# mds2.net
KiCad netlist of a schematic drawn in EAGLE
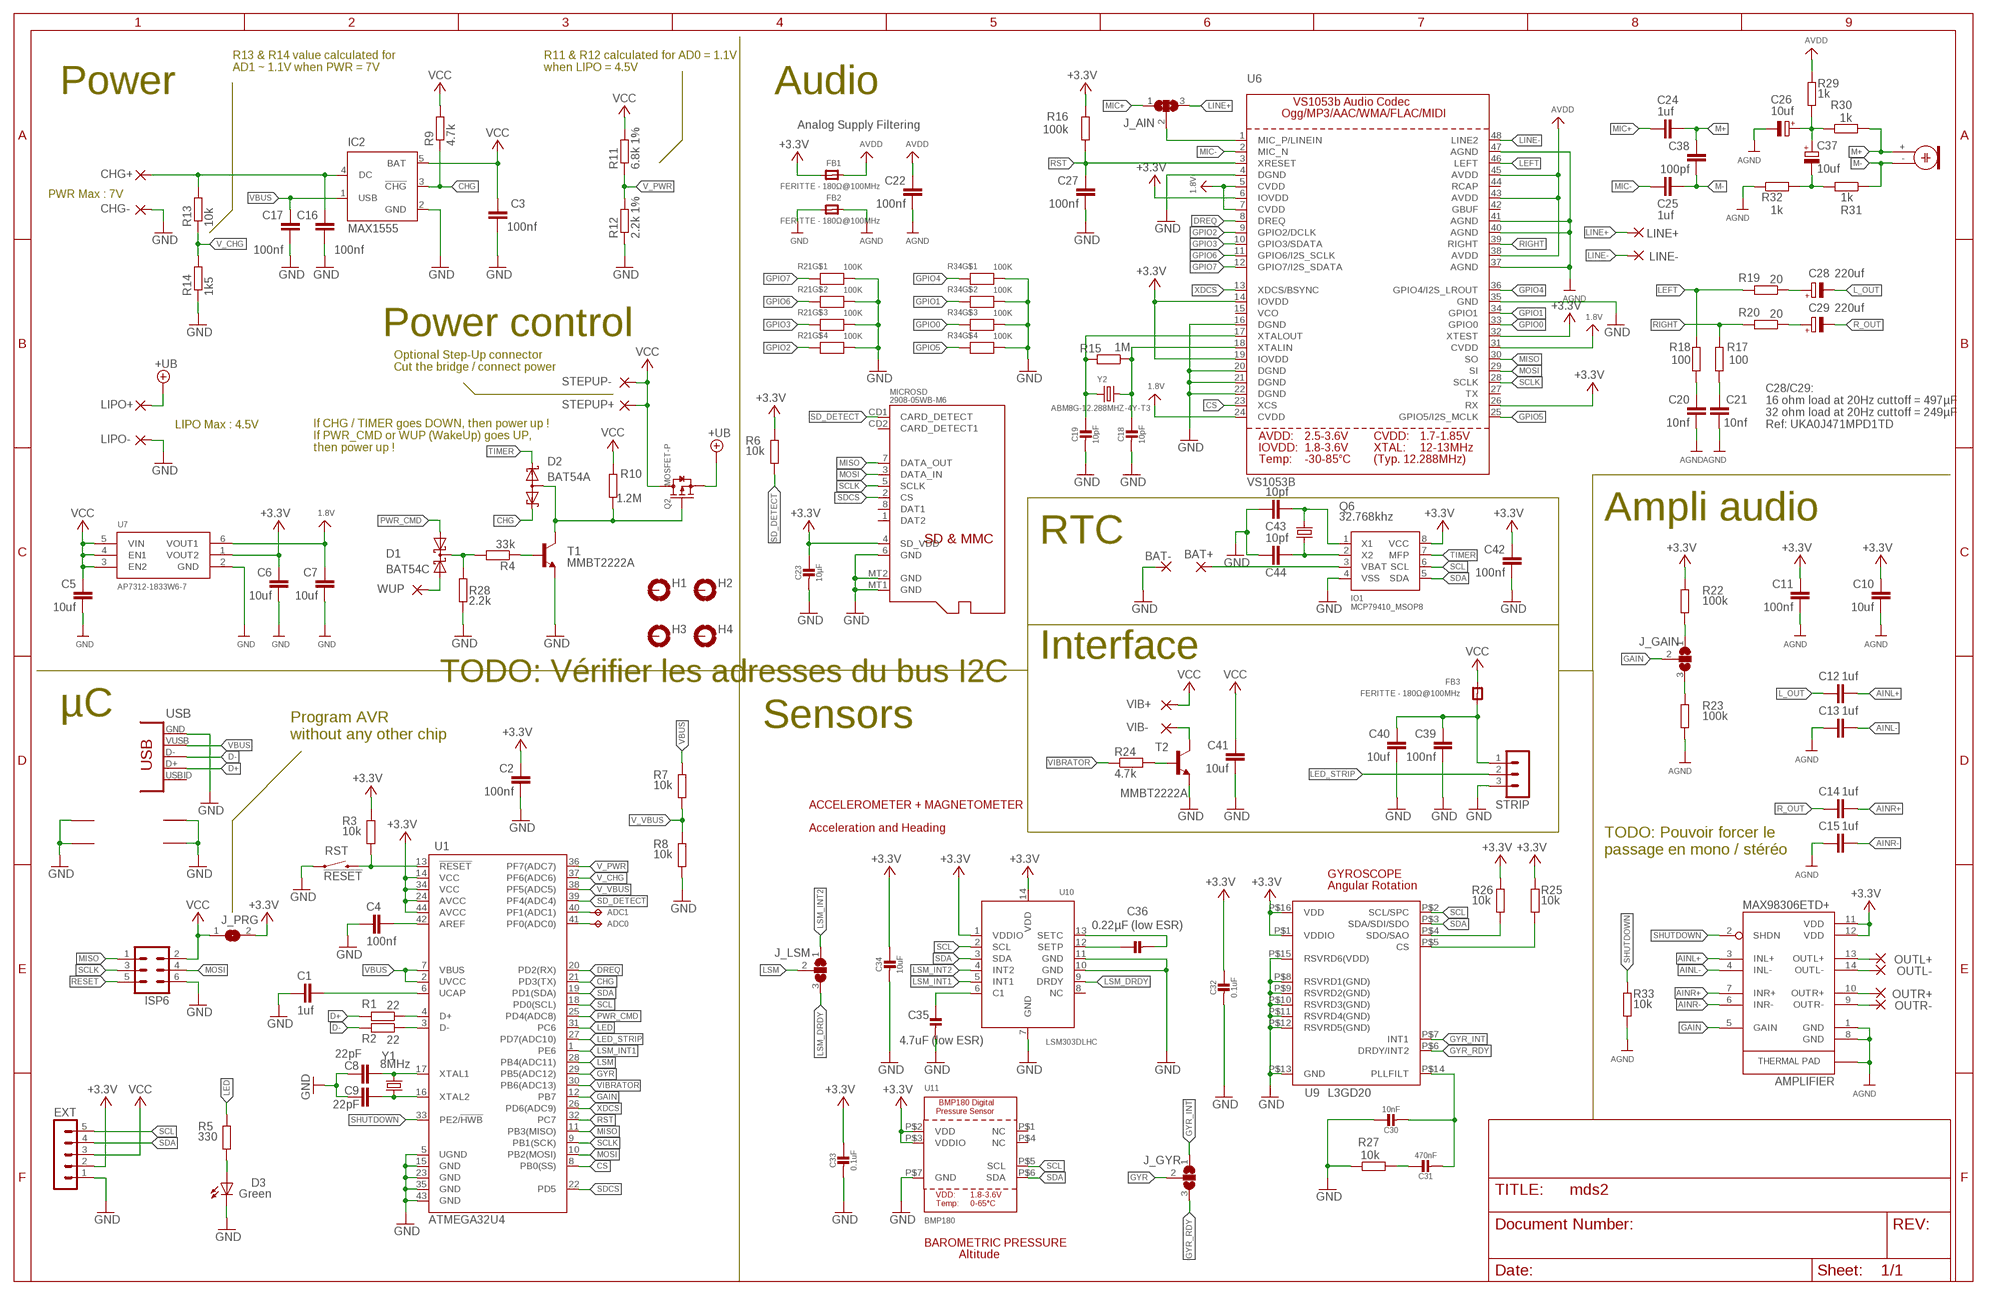
[diagram p0: schematic, sheet 1]

(export (version "E")
  (design (tool "Eeschema 10.0.6"))
  (components
    (comp (ref "ADC0")
      (value "TPB1,27")
      (footprint "eagle-import:B1,27")
      (libsource (lib "eagle-import") (part "TPB1,27"))
    )
    (comp (ref "ADC1")
      (value "TPB1,27")
      (footprint "eagle-import:B1,27")
      (libsource (lib "eagle-import") (part "TPB1,27"))
    )
    (comp (ref "AMPLIFIER")
      (value "MAX98306ETD+")
      (footprint "eagle-import:14-TDFN")
      (libsource (lib "eagle-import") (part "MAX98306ETD+"))
    )
    (comp (ref "BAT+")
      (value "1,6/0,8")
      (footprint "eagle-import:1,6_0,8")
      (libsource (lib "eagle-import") (part "1,6/0,8"))
    )
    (comp (ref "BAT-")
      (value "1,6/0,8")
      (footprint "eagle-import:1,6_0,8")
      (libsource (lib "eagle-import") (part "1,6/0,8"))
    )
    (comp (ref "C1")
      (value "1uf")
      (footprint "eagle-import:C0805")
      (libsource (lib "eagle-import") (part "C-EUC0805"))
    )
    (comp (ref "C2")
      (value "100nf")
      (footprint "eagle-import:C0805")
      (libsource (lib "eagle-import") (part "C-EUC0805"))
    )
    (comp (ref "C3")
      (value "100nf")
      (footprint "eagle-import:C0805")
      (libsource (lib "eagle-import") (part "C-EUC0805"))
    )
    (comp (ref "C4")
      (value "100nf")
      (footprint "eagle-import:C0805")
      (libsource (lib "eagle-import") (part "C-EUC0805"))
    )
    (comp (ref "C5")
      (value "10uf")
      (footprint "eagle-import:C0805")
      (libsource (lib "eagle-import") (part "C-EUC0805"))
    )
    (comp (ref "C6")
      (value "10uf")
      (footprint "eagle-import:C0805")
      (libsource (lib "eagle-import") (part "C-EUC0805"))
    )
    (comp (ref "C7")
      (value "10uf")
      (footprint "eagle-import:C0805")
      (libsource (lib "eagle-import") (part "C-EUC0805"))
    )
    (comp (ref "C8")
      (value "22pF")
      (footprint "eagle-import:0402-CAP")
      (libsource (lib "eagle-import") (part "CAP0402-CAP"))
    )
    (comp (ref "C9")
      (value "22pF")
      (footprint "eagle-import:0402-CAP")
      (libsource (lib "eagle-import") (part "CAP0402-CAP"))
    )
    (comp (ref "C10")
      (value "10uf")
      (footprint "eagle-import:C0805")
      (libsource (lib "eagle-import") (part "C-EUC0805"))
    )
    (comp (ref "C11")
      (value "100nf")
      (footprint "eagle-import:C0805")
      (libsource (lib "eagle-import") (part "C-EUC0805"))
    )
    (comp (ref "C12")
      (value "1uf")
      (footprint "eagle-import:C0805")
      (libsource (lib "eagle-import") (part "C-EUC0805"))
    )
    (comp (ref "C13")
      (value "1uf")
      (footprint "eagle-import:C0805")
      (libsource (lib "eagle-import") (part "C-EUC0805"))
    )
    (comp (ref "C14")
      (value "1uf")
      (footprint "eagle-import:C0805")
      (libsource (lib "eagle-import") (part "C-EUC0805"))
    )
    (comp (ref "C15")
      (value "1uf")
      (footprint "eagle-import:C0805")
      (libsource (lib "eagle-import") (part "C-EUC0805"))
    )
    (comp (ref "C16")
      (value "100nf")
      (footprint "eagle-import:C0805")
      (libsource (lib "eagle-import") (part "C-EUC0805"))
    )
    (comp (ref "C17")
      (value "100nf")
      (footprint "eagle-import:C0805")
      (libsource (lib "eagle-import") (part "C-EUC0805"))
    )
    (comp (ref "C18")
      (value "10pF")
      (footprint "eagle-import:_0805MP")
      (libsource (lib "eagle-import") (part "CAP_CERAMIC_0805MP"))
    )
    (comp (ref "C19")
      (value "10pF")
      (footprint "eagle-import:_0805MP")
      (libsource (lib "eagle-import") (part "CAP_CERAMIC_0805MP"))
    )
    (comp (ref "C20")
      (value "10nf")
      (footprint "eagle-import:C0805")
      (libsource (lib "eagle-import") (part "C-EUC0805"))
    )
    (comp (ref "C21")
      (value "10nf")
      (footprint "eagle-import:C0805")
      (libsource (lib "eagle-import") (part "C-EUC0805"))
    )
    (comp (ref "C22")
      (value "100nf")
      (footprint "eagle-import:C0805")
      (libsource (lib "eagle-import") (part "C-EUC0805"))
    )
    (comp (ref "C23")
      (value "10µF")
      (footprint "eagle-import:_0805MP")
      (libsource (lib "eagle-import") (part "CAP_CERAMIC_0805MP"))
    )
    (comp (ref "C24")
      (value "1uf")
      (footprint "eagle-import:C0805")
      (libsource (lib "eagle-import") (part "C-EUC0805"))
    )
    (comp (ref "C25")
      (value "1uf")
      (footprint "eagle-import:C0805")
      (libsource (lib "eagle-import") (part "C-EUC0805"))
    )
    (comp (ref "C26")
      (value "10uf")
      (footprint "eagle-import:PANASONIC_C")
      (libsource (lib "eagle-import") (part "CPOL-EUC"))
    )
    (comp (ref "C27")
      (value "100nf")
      (footprint "eagle-import:C0805")
      (libsource (lib "eagle-import") (part "C-EUC0805"))
    )
    (comp (ref "C28")
      (value "220uf")
      (footprint "eagle-import:PANASONIC_D")
      (libsource (lib "eagle-import") (part "CPOL-EUD"))
    )
    (comp (ref "C29")
      (value "220uf")
      (footprint "eagle-import:PANASONIC_D")
      (libsource (lib "eagle-import") (part "CPOL-EUD"))
    )
    (comp (ref "C30")
      (value "10nF")
      (footprint "eagle-import:_0805MP")
      (libsource (lib "eagle-import") (part "CAP_CERAMIC_0805MP"))
    )
    (comp (ref "C31")
      (value "470nF")
      (footprint "eagle-import:_0805MP")
      (libsource (lib "eagle-import") (part "CAP_CERAMIC_0805MP"))
    )
    (comp (ref "C32")
      (value "0.1uF")
      (footprint "eagle-import:_0805MP")
      (libsource (lib "eagle-import") (part "CAP_CERAMIC_0805MP"))
    )
    (comp (ref "C33")
      (value "0.1uF")
      (footprint "eagle-import:_0805MP")
      (libsource (lib "eagle-import") (part "CAP_CERAMIC_0805MP"))
    )
    (comp (ref "C34")
      (value "10uF")
      (footprint "eagle-import:_0805MP")
      (libsource (lib "eagle-import") (part "CAP_CERAMIC_0805MP"))
    )
    (comp (ref "C35")
      (value "4.7uF (low ESR)")
      (footprint "eagle-import:_0805MP")
      (libsource (lib "eagle-import") (part "CAP_CERAMIC_0805MP"))
    )
    (comp (ref "C36")
      (value "0.22µF (low ESR)")
      (footprint "eagle-import:_0805MP")
      (libsource (lib "eagle-import") (part "CAP_CERAMIC_0805MP"))
    )
    (comp (ref "C37")
      (value "10uf")
      (footprint "eagle-import:PANASONIC_C")
      (libsource (lib "eagle-import") (part "CPOL-EUC"))
    )
    (comp (ref "C38")
      (value "100pf")
      (footprint "eagle-import:C0805")
      (libsource (lib "eagle-import") (part "C-EUC0805"))
    )
    (comp (ref "C39")
      (value "100nf")
      (footprint "eagle-import:C0805")
      (libsource (lib "eagle-import") (part "C-EUC0805"))
    )
    (comp (ref "C40")
      (value "10uf")
      (footprint "eagle-import:C0805")
      (libsource (lib "eagle-import") (part "C-EUC0805"))
    )
    (comp (ref "C41")
      (value "10uf")
      (footprint "eagle-import:C0805")
      (libsource (lib "eagle-import") (part "C-EUC0805"))
    )
    (comp (ref "C42")
      (value "100nf")
      (footprint "eagle-import:C0805")
      (libsource (lib "eagle-import") (part "C-EUC0805"))
    )
    (comp (ref "C43")
      (value "10pf")
      (footprint "eagle-import:C0805")
      (libsource (lib "eagle-import") (part "C-EUC0805"))
    )
    (comp (ref "C44")
      (value "10pf")
      (footprint "eagle-import:C0805")
      (libsource (lib "eagle-import") (part "C-EUC0805"))
    )
    (comp (ref "CHG+")
      (value "2,15/1,0")
      (footprint "eagle-import:2,15_1,0")
      (libsource (lib "eagle-import") (part "2,15/1,0"))
    )
    (comp (ref "CHG-")
      (value "2,15/1,0")
      (footprint "eagle-import:2,15_1,0")
      (libsource (lib "eagle-import") (part "2,15/1,0"))
    )
    (comp (ref "D1")
      (value "BAT54C")
      (footprint "eagle-import:SOT23")
      (libsource (lib "eagle-import") (part "BAT54C"))
    )
    (comp (ref "D2")
      (value "BAT54A")
      (footprint "eagle-import:SOT23")
      (libsource (lib "eagle-import") (part "BAT54A"))
    )
    (comp (ref "D3")
      (value "Green")
      (footprint "eagle-import:LED-0603")
      (libsource (lib "eagle-import") (part "LED0603"))
    )
    (comp (ref "EXT")
      (value "MA05-1")
      (footprint "eagle-import:MA05-1")
      (libsource (lib "eagle-import") (part "MA05-1"))
    )
    (comp (ref "FB1")
      (value "FERITTE - 180Ω@100MHz")
      (footprint "eagle-import:_0805MP")
      (libsource (lib "eagle-import") (part "FERRITE_0805MP"))
    )
    (comp (ref "FB2")
      (value "FERITTE - 180Ω@100MHz")
      (footprint "eagle-import:_0805MP")
      (libsource (lib "eagle-import") (part "FERRITE_0805MP"))
    )
    (comp (ref "FB3")
      (value "FERITTE - 180Ω@100MHz")
      (footprint "eagle-import:_0805MP")
      (libsource (lib "eagle-import") (part "FERRITE_0805MP"))
    )
    (comp (ref "H1")
      (value "MOUNT-PAD-ROUND3.0")
      (footprint "eagle-import:3,0-PAD")
      (libsource (lib "eagle-import") (part "MOUNT-PAD-ROUND3.0"))
    )
    (comp (ref "H2")
      (value "MOUNT-PAD-ROUND3.0")
      (footprint "eagle-import:3,0-PAD")
      (libsource (lib "eagle-import") (part "MOUNT-PAD-ROUND3.0"))
    )
    (comp (ref "H3")
      (value "MOUNT-PAD-ROUND3.0")
      (footprint "eagle-import:3,0-PAD")
      (libsource (lib "eagle-import") (part "MOUNT-PAD-ROUND3.0"))
    )
    (comp (ref "H4")
      (value "MOUNT-PAD-ROUND3.0")
      (footprint "eagle-import:3,0-PAD")
      (libsource (lib "eagle-import") (part "MOUNT-PAD-ROUND3.0"))
    )
    (comp (ref "IC2")
      (value "MAX1555")
      (footprint "eagle-import:SOT23-5L")
      (fields (field (name "MF") "MAXIM") (field (name "MPN") "MAX1555EZK+T"))
      (libsource (lib "eagle-import") (part "MAX1555"))
    )
    (comp (ref "IO1")
      (value "MCP79410_MSOP8")
      (footprint "eagle-import:MSOP8")
      (fields (field (name "MPN") "MCP79410-I/MS"))
      (libsource (lib "eagle-import") (part "MCP79410_MSOP8"))
    )
    (comp (ref "ISP6")
      (value "MA03-2")
      (footprint "eagle-import:MA03-2")
      (libsource (lib "eagle-import") (part "MA03-2"))
    )
    (comp (ref "J_AIN")
      (value "SJ2W")
      (footprint "eagle-import:SJ_2")
      (libsource (lib "eagle-import") (part "SJ2W"))
    )
    (comp (ref "J_GAIN")
      (value "SJ2W")
      (footprint "eagle-import:SJ_2")
      (libsource (lib "eagle-import") (part "SJ2W"))
    )
    (comp (ref "J_GYR")
      (value "SJ2W")
      (footprint "eagle-import:SJ_2")
      (libsource (lib "eagle-import") (part "SJ2W"))
    )
    (comp (ref "J_LSM")
      (value "SJ2W")
      (footprint "eagle-import:SJ_2")
      (libsource (lib "eagle-import") (part "SJ2W"))
    )
    (comp (ref "J_PRG")
      (value "SJ")
      (footprint "eagle-import:SJ")
      (libsource (lib "eagle-import") (part "SJ"))
    )
    (comp (ref "LINE+")
      (value "1,6/0,8")
      (footprint "eagle-import:1,6_0,8")
      (libsource (lib "eagle-import") (part "1,6/0,8"))
    )
    (comp (ref "LINE-")
      (value "1,6/0,8")
      (footprint "eagle-import:1,6_0,8")
      (libsource (lib "eagle-import") (part "1,6/0,8"))
    )
    (comp (ref "LIPO+")
      (value "2,15/1,0")
      (footprint "eagle-import:2,15_1,0")
      (libsource (lib "eagle-import") (part "2,15/1,0"))
    )
    (comp (ref "LIPO-")
      (value "2,15/1,0")
      (footprint "eagle-import:2,15_1,0")
      (libsource (lib "eagle-import") (part "2,15/1,0"))
    )
    (comp (ref "MIC")
      (value "ELECTRET_MICROPHON-TOM-1545P-R")
      (footprint "eagle-import:TOM-1545P-R")
      (libsource (lib "eagle-import") (part "ELECTRET_MICROPHON-TOM-1545P-R"))
    )
    (comp (ref "MICROSD")
      (value "2908-05WB-M6")
      (footprint "eagle-import:MICROSD")
      (libsource (lib "eagle-import") (part "MICROSD"))
    )
    (comp (ref "OUTL+")
      (value "2,15/1,0")
      (footprint "eagle-import:2,15_1,0")
      (libsource (lib "eagle-import") (part "2,15/1,0"))
    )
    (comp (ref "OUTL-")
      (value "2,15/1,0")
      (footprint "eagle-import:2,15_1,0")
      (libsource (lib "eagle-import") (part "2,15/1,0"))
    )
    (comp (ref "OUTR+")
      (value "2,15/1,0")
      (footprint "eagle-import:2,15_1,0")
      (libsource (lib "eagle-import") (part "2,15/1,0"))
    )
    (comp (ref "OUTR-")
      (value "2,15/1,0")
      (footprint "eagle-import:2,15_1,0")
      (libsource (lib "eagle-import") (part "2,15/1,0"))
    )
    (comp (ref "Q2")
      (value "MOSFET-P")
      (footprint "eagle-import:SOT23")
      (libsource (lib "eagle-import") (part "MOSFET-P-044021001"))
    )
    (comp (ref "Q6")
      (value "32.768khz")
      (footprint "eagle-import:TC26H")
      (libsource (lib "eagle-import") (part "crystal_CRYSTALTC26H"))
    )
    (comp (ref "R1")
      (value "22")
      (footprint "eagle-import:M0805")
      (libsource (lib "eagle-import") (part "R-EU_M0805"))
    )
    (comp (ref "R2")
      (value "22")
      (footprint "eagle-import:M0805")
      (libsource (lib "eagle-import") (part "R-EU_M0805"))
    )
    (comp (ref "R3")
      (value "10k")
      (footprint "eagle-import:M0805")
      (libsource (lib "eagle-import") (part "R-EU_M0805"))
    )
    (comp (ref "R4")
      (value "33k")
      (footprint "eagle-import:M0805")
      (libsource (lib "eagle-import") (part "R-EU_M0805"))
    )
    (comp (ref "R5")
      (value "330")
      (footprint "eagle-import:M0805")
      (libsource (lib "eagle-import") (part "R-EU_M0805"))
    )
    (comp (ref "R6")
      (value "10k")
      (footprint "eagle-import:M0805")
      (libsource (lib "eagle-import") (part "R-EU_M0805"))
    )
    (comp (ref "R7")
      (value "10k")
      (footprint "eagle-import:M0805")
      (libsource (lib "eagle-import") (part "R-EU_M0805"))
    )
    (comp (ref "R8")
      (value "10k")
      (footprint "eagle-import:M0805")
      (libsource (lib "eagle-import") (part "R-EU_M0805"))
    )
    (comp (ref "R9")
      (value "4.7k")
      (footprint "eagle-import:M0805")
      (libsource (lib "eagle-import") (part "R-EU_M0805"))
    )
    (comp (ref "R10")
      (value "1.2M")
      (footprint "eagle-import:M0805")
      (libsource (lib "eagle-import") (part "R-EU_M0805"))
    )
    (comp (ref "R11")
      (value "6.8k 1%")
      (footprint "eagle-import:M0805")
      (libsource (lib "eagle-import") (part "R-EU_M0805"))
    )
    (comp (ref "R12")
      (value "2.2k 1%")
      (footprint "eagle-import:M0805")
      (libsource (lib "eagle-import") (part "R-EU_M0805"))
    )
    (comp (ref "R13")
      (value "10k")
      (footprint "eagle-import:M0805")
      (libsource (lib "eagle-import") (part "R-EU_M0805"))
    )
    (comp (ref "R14")
      (value "1k5")
      (footprint "eagle-import:M0805")
      (libsource (lib "eagle-import") (part "R-EU_M0805"))
    )
    (comp (ref "R15")
      (value "1M")
      (footprint "eagle-import:M0805")
      (libsource (lib "eagle-import") (part "R-EU_M0805"))
    )
    (comp (ref "R16")
      (value "100k")
      (footprint "eagle-import:M0805")
      (libsource (lib "eagle-import") (part "R-EU_M0805"))
    )
    (comp (ref "R17")
      (value "100")
      (footprint "eagle-import:M0805")
      (libsource (lib "eagle-import") (part "R-EU_M0805"))
    )
    (comp (ref "R18")
      (value "100")
      (footprint "eagle-import:M0805")
      (libsource (lib "eagle-import") (part "R-EU_M0805"))
    )
    (comp (ref "R19")
      (value "20")
      (footprint "eagle-import:M0805")
      (libsource (lib "eagle-import") (part "R-EU_M0805"))
    )
    (comp (ref "R20")
      (value "20")
      (footprint "eagle-import:M0805")
      (libsource (lib "eagle-import") (part "R-EU_M0805"))
    )
    (comp (ref "R21")
      (value "100K")
      (footprint "eagle-import:RESPACK_4X0603")
      (libsource (lib "eagle-import") (part "RESISTOR_4PACK"))
    )
    (comp (ref "R22")
      (value "100k")
      (footprint "eagle-import:M0805")
      (libsource (lib "eagle-import") (part "R-EU_M0805"))
    )
    (comp (ref "R23")
      (value "100k")
      (footprint "eagle-import:M0805")
      (libsource (lib "eagle-import") (part "R-EU_M0805"))
    )
    (comp (ref "R24")
      (value "4.7k")
      (footprint "eagle-import:M0805")
      (libsource (lib "eagle-import") (part "R-EU_M0805"))
    )
    (comp (ref "R25")
      (value "10k")
      (footprint "eagle-import:M0805")
      (libsource (lib "eagle-import") (part "R-EU_M0805"))
    )
    (comp (ref "R26")
      (value "10k")
      (footprint "eagle-import:M0805")
      (libsource (lib "eagle-import") (part "R-EU_M0805"))
    )
    (comp (ref "R27")
      (value "10k")
      (footprint "eagle-import:M0805")
      (libsource (lib "eagle-import") (part "R-EU_M0805"))
    )
    (comp (ref "R28")
      (value "2.2k")
      (footprint "eagle-import:M0805")
      (libsource (lib "eagle-import") (part "R-EU_M0805"))
    )
    (comp (ref "R29")
      (value "1k")
      (footprint "eagle-import:M0805")
      (libsource (lib "eagle-import") (part "R-EU_M0805"))
    )
    (comp (ref "R30")
      (value "1k")
      (footprint "eagle-import:M0805")
      (libsource (lib "eagle-import") (part "R-EU_M0805"))
    )
    (comp (ref "R31")
      (value "1k")
      (footprint "eagle-import:M0805")
      (libsource (lib "eagle-import") (part "R-EU_M0805"))
    )
    (comp (ref "R32")
      (value "1k")
      (footprint "eagle-import:M0805")
      (libsource (lib "eagle-import") (part "R-EU_M0805"))
    )
    (comp (ref "R33")
      (value "10k")
      (footprint "eagle-import:M0805")
      (libsource (lib "eagle-import") (part "R-EU_M0805"))
    )
    (comp (ref "R34")
      (value "100K")
      (footprint "eagle-import:RESPACK_4X0603")
      (libsource (lib "eagle-import") (part "RESISTOR_4PACK"))
    )
    (comp (ref "RST")
      (value "!RESET")
      (footprint "eagle-import:TACTILE_SWITCH_SMD")
      (libsource (lib "eagle-import") (part "SWITCH-MOMENTARY-2SMD"))
    )
    (comp (ref "STEPUP+")
      (value "2,15/1,0")
      (footprint "eagle-import:2,15_1,0")
      (libsource (lib "eagle-import") (part "2,15/1,0"))
    )
    (comp (ref "STEPUP-")
      (value "2,15/1,0")
      (footprint "eagle-import:2,15_1,0")
      (libsource (lib "eagle-import") (part "2,15/1,0"))
    )
    (comp (ref "STRIP")
      (value "MA03-1")
      (footprint "eagle-import:MA03-1")
      (libsource (lib "eagle-import") (part "MA03-1"))
    )
    (comp (ref "T1")
      (value "MMBT2222A")
      (footprint "eagle-import:SOT23-BEC")
      (libsource (lib "eagle-import") (part "-NPN-SOT23-BECMMBT2222ALT1"))
    )
    (comp (ref "T2")
      (value "MMBT2222A")
      (footprint "eagle-import:SOT23-BEC")
      (libsource (lib "eagle-import") (part "-NPN-SOT23-BECMMBT2222ALT1"))
    )
    (comp (ref "U1")
      (value "ATMEGA32U4")
      (footprint "eagle-import:QFN-44-NOPAD")
      (libsource (lib "eagle-import") (part "ATMEGA32U4QFN2"))
    )
    (comp (ref "U6")
      (value "VS1053B")
      (footprint "eagle-import:LQFP48")
      (libsource (lib "eagle-import") (part "VS1053B"))
    )
    (comp (ref "U7")
      (value "AP7312-1833W6-7")
      (footprint "eagle-import:SOT23-6")
      (libsource (lib "eagle-import") (part "VREG_SOT23-6_DUALAP7312"))
    )
    (comp (ref "U9")
      (value "L3GD20")
      (footprint "eagle-import:L3G4200D_LGA16L")
      (libsource (lib "eagle-import") (part "GYRO_L3G2400D"))
    )
    (comp (ref "U10")
      (value "LSM303DLHC")
      (footprint "eagle-import:LGA14")
      (libsource (lib "eagle-import") (part "LSM303DLHC"))
    )
    (comp (ref "U11")
      (value "BMP180")
      (footprint "eagle-import:BMP180_EXTENDED")
      (libsource (lib "eagle-import") (part "BMP180EXT"))
    )
    (comp (ref "USB")
      (value "CON-USB-F-MICRO-B")
      (footprint "eagle-import:CONN_USB_MICRO-B")
      (libsource (lib "eagle-import") (part "CON-USB-F-MICRO-B"))
    )
    (comp (ref "VIB+")
      (value "1,6/0,8")
      (footprint "eagle-import:1,6_0,8")
      (libsource (lib "eagle-import") (part "1,6/0,8"))
    )
    (comp (ref "VIB-")
      (value "1,6/0,8")
      (footprint "eagle-import:1,6_0,8")
      (libsource (lib "eagle-import") (part "1,6/0,8"))
    )
    (comp (ref "WUP")
      (value "1,6/0,8")
      (footprint "eagle-import:1,6_0,8")
      (libsource (lib "eagle-import") (part "1,6/0,8"))
    )
    (comp (ref "Y1")
      (value "8MHz")
      (footprint "eagle-import:CRYSTAL-SMD-5X3")
      (libsource (lib "eagle-import") (part "CRYSTAL5X3"))
    )
    (comp (ref "Y2")
      (value "ABM8G-12.288MHZ-4Y-T3")
      (footprint "eagle-import:CRYSTAL_3.2X2.5")
      (libsource (lib "eagle-import") (part "CRYSTAL3.2X2.5"))
    )
  )
  (nets
    (net (code "1") (name "+3.3V") (class "Default")
      (node (ref "AMPLIFIER") (pin "11") (pinfunction "VDD_11") (pintype "power_in"))
      (node (ref "AMPLIFIER") (pin "12") (pinfunction "VDD_12") (pintype "power_in"))
      (node (ref "C10") (pin "2") (pinfunction "2_2") (pintype "passive"))
      (node (ref "C11") (pin "2") (pinfunction "2_2") (pintype "passive"))
      (node (ref "C2") (pin "2") (pinfunction "2_2") (pintype "passive"))
      (node (ref "C23") (pin "1") (pinfunction "1_1") (pintype "passive"))
      (node (ref "C32") (pin "1") (pinfunction "1_1") (pintype "passive"))
      (node (ref "C33") (pin "1") (pinfunction "1_1") (pintype "passive"))
      (node (ref "C34") (pin "1") (pinfunction "1_1") (pintype "passive"))
      (node (ref "C42") (pin "2") (pinfunction "2_2") (pintype "passive"))
      (node (ref "C6") (pin "2") (pinfunction "2_2") (pintype "passive"))
      (node (ref "EXT") (pin "2") (pinfunction "2_2") (pintype "passive"))
      (node (ref "FB1") (pin "1") (pinfunction "P$1_1") (pintype "passive"))
      (node (ref "IO1") (pin "8") (pinfunction "VCC_8") (pintype "bidirectional"))
      (node (ref "J_PRG") (pin "2") (pinfunction "2_2") (pintype "passive"))
      (node (ref "MICROSD") (pin "4") (pinfunction "SD_VDD_4") (pintype "power_in"))
      (node (ref "R16") (pin "2") (pinfunction "2_2") (pintype "passive"))
      (node (ref "R22") (pin "2") (pinfunction "2_2") (pintype "passive"))
      (node (ref "R25") (pin "2") (pinfunction "2_2") (pintype "passive"))
      (node (ref "R26") (pin "2") (pinfunction "2_2") (pintype "passive"))
      (node (ref "R3") (pin "1") (pinfunction "1_1") (pintype "passive"))
      (node (ref "R6") (pin "1") (pinfunction "1_1") (pintype "passive"))
      (node (ref "U1") (pin "14") (pinfunction "VCC_14") (pintype "bidirectional"))
      (node (ref "U1") (pin "24") (pinfunction "AVCC_24") (pintype "bidirectional"))
      (node (ref "U1") (pin "34") (pinfunction "VCC_34") (pintype "bidirectional"))
      (node (ref "U1") (pin "44") (pinfunction "AVCC_44") (pintype "bidirectional"))
      (node (ref "U10") (pin "1") (pinfunction "VDDIO_1") (pintype "power_in"))
      (node (ref "U10") (pin "14") (pinfunction "VDD_14") (pintype "power_in"))
      (node (ref "U11") (pin "P$2") (pinfunction "VDD_P$2") (pintype "power_in"))
      (node (ref "U11") (pin "P$3") (pinfunction "VDDIO_P$3") (pintype "power_in"))
      (node (ref "U6") (pin "14") (pinfunction "IOVDD_14") (pintype "power_in"))
      (node (ref "U6") (pin "19") (pinfunction "IOVDD_19") (pintype "power_in"))
      (node (ref "U6") (pin "26") (pinfunction "RX_26") (pintype "bidirectional"))
      (node (ref "U6") (pin "32") (pinfunction "XTEST_32") (pintype "bidirectional"))
      (node (ref "U6") (pin "6") (pinfunction "IOVDD_6") (pintype "power_in"))
      (node (ref "U7") (pin "1") (pinfunction "VOUT2_1") (pintype "bidirectional"))
      (node (ref "U9") (pin "P$1") (pinfunction "VDDIO_P$1") (pintype "power_in"))
      (node (ref "U9") (pin "P$16") (pinfunction "VDD_P$16") (pintype "bidirectional"))
    )
    (net (code "2") (name "+UB") (class "Default")
      (node (ref "LIPO+") (pin "1") (pinfunction "P_1") (pintype "passive"))
      (node (ref "Q2") (pin "2") (pinfunction "S_2") (pintype "passive"))
    )
    (net (code "3") (name "1.8V") (class "Default")
      (node (ref "C7") (pin "2") (pinfunction "2_2") (pintype "passive"))
      (node (ref "U6") (pin "24") (pinfunction "CVDD_24") (pintype "power_in"))
      (node (ref "U6") (pin "31") (pinfunction "CVDD_31") (pintype "power_in"))
      (node (ref "U6") (pin "5") (pinfunction "CVDD_5") (pintype "power_in"))
      (node (ref "U6") (pin "7") (pinfunction "CVDD_7") (pintype "power_in"))
      (node (ref "U7") (pin "6") (pinfunction "VOUT1_6") (pintype "bidirectional"))
    )
    (net (code "4") (name "AGND") (class "Default")
      (node (ref "AMPLIFIER") (pin "1") (pinfunction "GND_1") (pintype "power_in"))
      (node (ref "AMPLIFIER") (pin "15") (pinfunction "GND_15") (pintype "power_in"))
      (node (ref "AMPLIFIER") (pin "8") (pinfunction "GND_8") (pintype "power_in"))
      (node (ref "C10") (pin "1") (pinfunction "1_1") (pintype "passive"))
      (node (ref "C11") (pin "1") (pinfunction "1_1") (pintype "passive"))
      (node (ref "C13") (pin "2") (pinfunction "2_2") (pintype "passive"))
      (node (ref "C15") (pin "2") (pinfunction "2_2") (pintype "passive"))
      (node (ref "C20") (pin "1") (pinfunction "1_1") (pintype "passive"))
      (node (ref "C21") (pin "1") (pinfunction "1_1") (pintype "passive"))
      (node (ref "C22") (pin "1") (pinfunction "1_1") (pintype "passive"))
      (node (ref "C26") (pin "-") (pinfunction "-_-") (pintype "passive"))
      (node (ref "FB2") (pin "2") (pinfunction "P$2_2") (pintype "passive"))
      (node (ref "R23") (pin "1") (pinfunction "1_1") (pintype "passive"))
      (node (ref "R32") (pin "1") (pinfunction "1_1") (pintype "passive"))
      (node (ref "R33") (pin "1") (pinfunction "1_1") (pintype "passive"))
      (node (ref "U6") (pin "37") (pinfunction "AGND_37") (pintype "power_in"))
      (node (ref "U6") (pin "40") (pinfunction "AGND_40") (pintype "power_in"))
      (node (ref "U6") (pin "41") (pinfunction "AGND_41") (pintype "power_in"))
      (node (ref "U6") (pin "47") (pinfunction "AGND_47") (pintype "power_in"))
    )
    (net (code "5") (name "AINL+") (class "Default")
      (node (ref "AMPLIFIER") (pin "3") (pinfunction "INL+_3") (pintype "bidirectional"))
      (node (ref "C12") (pin "1") (pinfunction "1_1") (pintype "passive"))
    )
    (net (code "6") (name "AINL-") (class "Default")
      (node (ref "AMPLIFIER") (pin "4") (pinfunction "INL-_4") (pintype "bidirectional"))
      (node (ref "C13") (pin "1") (pinfunction "1_1") (pintype "passive"))
    )
    (net (code "7") (name "AINR+") (class "Default")
      (node (ref "AMPLIFIER") (pin "7") (pinfunction "INR+_7") (pintype "bidirectional"))
      (node (ref "C14") (pin "1") (pinfunction "1_1") (pintype "passive"))
    )
    (net (code "8") (name "AINR-") (class "Default")
      (node (ref "AMPLIFIER") (pin "6") (pinfunction "INR-_6") (pintype "bidirectional"))
      (node (ref "C15") (pin "1") (pinfunction "1_1") (pintype "passive"))
    )
    (net (code "9") (name "AVDD") (class "Default")
      (node (ref "C22") (pin "2") (pinfunction "2_2") (pintype "passive"))
      (node (ref "FB1") (pin "2") (pinfunction "P$2_2") (pintype "passive"))
      (node (ref "R29") (pin "2") (pinfunction "2_2") (pintype "passive"))
      (node (ref "U6") (pin "38") (pinfunction "AVDD_38") (pintype "power_in"))
      (node (ref "U6") (pin "43") (pinfunction "AVDD_43") (pintype "power_in"))
      (node (ref "U6") (pin "45") (pinfunction "AVDD_45") (pintype "power_in"))
    )
    (net (code "10") (name "CHG") (class "Default")
      (node (ref "D2") (pin "2") (pinfunction "K2_2") (pintype "passive"))
      (node (ref "IC2") (pin "3") (pinfunction "~{CHG}_3") (pintype "output"))
      (node (ref "R9") (pin "1") (pinfunction "1_1") (pintype "passive"))
      (node (ref "U1") (pin "21") (pinfunction "PD3(TX)_21") (pintype "bidirectional"))
    )
    (net (code "11") (name "CS") (class "Default")
      (node (ref "U1") (pin "8") (pinfunction "PB0(SS)_8") (pintype "bidirectional"))
      (node (ref "U6") (pin "23") (pinfunction "XCS_23") (pintype "bidirectional"))
    )
    (net (code "12") (name "D+") (class "Default")
      (node (ref "R1") (pin "2") (pinfunction "2_2") (pintype "passive"))
      (node (ref "USB") (pin "P3") (pinfunction "D+_P3") (pintype "bidirectional"))
    )
    (net (code "13") (name "D-") (class "Default")
      (node (ref "R2") (pin "2") (pinfunction "2_2") (pintype "passive"))
      (node (ref "USB") (pin "P2") (pinfunction "D-_P2") (pintype "bidirectional"))
    )
    (net (code "14") (name "DREQ") (class "Default")
      (node (ref "U1") (pin "20") (pinfunction "PD2(RX)_20") (pintype "bidirectional"))
      (node (ref "U6") (pin "8") (pinfunction "DREQ_8") (pintype "bidirectional"))
    )
    (net (code "15") (name "GAIN") (class "Default")
      (node (ref "AMPLIFIER") (pin "5") (pinfunction "GAIN_5") (pintype "passive"))
      (node (ref "J_GAIN") (pin "2") (pinfunction "2_2") (pintype "passive"))
      (node (ref "U1") (pin "12") (pinfunction "PB7_12") (pintype "bidirectional"))
    )
    (net (code "16") (name "GND") (class "Default")
      (node (ref "BAT-") (pin "1") (pinfunction "P_1") (pintype "passive"))
      (node (ref "C1") (pin "2") (pinfunction "2_2") (pintype "passive"))
      (node (ref "C16") (pin "1") (pinfunction "1_1") (pintype "passive"))
      (node (ref "C17") (pin "1") (pinfunction "1_1") (pintype "passive"))
      (node (ref "C18") (pin "2") (pinfunction "2_2") (pintype "passive"))
      (node (ref "C19") (pin "2") (pinfunction "2_2") (pintype "passive"))
      (node (ref "C2") (pin "1") (pinfunction "1_1") (pintype "passive"))
      (node (ref "C23") (pin "2") (pinfunction "2_2") (pintype "passive"))
      (node (ref "C27") (pin "1") (pinfunction "1_1") (pintype "passive"))
      (node (ref "C3") (pin "1") (pinfunction "1_1") (pintype "passive"))
      (node (ref "C30") (pin "1") (pinfunction "1_1") (pintype "passive"))
      (node (ref "C32") (pin "2") (pinfunction "2_2") (pintype "passive"))
      (node (ref "C33") (pin "2") (pinfunction "2_2") (pintype "passive"))
      (node (ref "C34") (pin "2") (pinfunction "2_2") (pintype "passive"))
      (node (ref "C35") (pin "2") (pinfunction "2_2") (pintype "passive"))
      (node (ref "C39") (pin "1") (pinfunction "1_1") (pintype "passive"))
      (node (ref "C4") (pin "2") (pinfunction "2_2") (pintype "passive"))
      (node (ref "C40") (pin "1") (pinfunction "1_1") (pintype "passive"))
      (node (ref "C41") (pin "1") (pinfunction "1_1") (pintype "passive"))
      (node (ref "C42") (pin "1") (pinfunction "1_1") (pintype "passive"))
      (node (ref "C43") (pin "2") (pinfunction "2_2") (pintype "passive"))
      (node (ref "C44") (pin "2") (pinfunction "2_2") (pintype "passive"))
      (node (ref "C5") (pin "1") (pinfunction "1_1") (pintype "passive"))
      (node (ref "C6") (pin "1") (pinfunction "1_1") (pintype "passive"))
      (node (ref "C7") (pin "1") (pinfunction "1_1") (pintype "passive"))
      (node (ref "C8") (pin "2") (pinfunction "2_2") (pintype "passive"))
      (node (ref "C9") (pin "2") (pinfunction "2_2") (pintype "passive"))
      (node (ref "CHG-") (pin "1") (pinfunction "P_1") (pintype "passive"))
      (node (ref "D3") (pin "C") (pinfunction "C_C") (pintype "passive"))
      (node (ref "EXT") (pin "1") (pinfunction "1_1") (pintype "passive"))
      (node (ref "FB2") (pin "1") (pinfunction "P$1_1") (pintype "passive"))
      (node (ref "IC2") (pin "2") (pinfunction "GND_2") (pintype "power_in"))
      (node (ref "IO1") (pin "4") (pinfunction "VSS_4") (pintype "bidirectional"))
      (node (ref "ISP6") (pin "6") (pinfunction "6_6") (pintype "passive"))
      (node (ref "LIPO-") (pin "1") (pinfunction "P_1") (pintype "passive"))
      (node (ref "MICROSD") (pin "6") (pinfunction "GND_6") (pintype "power_in"))
      (node (ref "MICROSD") (pin "MT1") (pinfunction "GND_MT1") (pintype "power_in"))
      (node (ref "MICROSD") (pin "MT2") (pinfunction "GND_MT2") (pintype "power_in"))
      (node (ref "R12") (pin "1") (pinfunction "1_1") (pintype "passive"))
      (node (ref "R14") (pin "1") (pinfunction "1_1") (pintype "passive"))
      (node (ref "R21") (pin "5") (pinfunction "2_5") (pintype "passive"))
      (node (ref "R21") (pin "6") (pinfunction "2_6") (pintype "passive"))
      (node (ref "R21") (pin "7") (pinfunction "2_7") (pintype "passive"))
      (node (ref "R21") (pin "8") (pinfunction "2_8") (pintype "passive"))
      (node (ref "R27") (pin "1") (pinfunction "1_1") (pintype "passive"))
      (node (ref "R28") (pin "2") (pinfunction "2_2") (pintype "passive"))
      (node (ref "R34") (pin "5") (pinfunction "2_5") (pintype "passive"))
      (node (ref "R34") (pin "6") (pinfunction "2_6") (pintype "passive"))
      (node (ref "R34") (pin "7") (pinfunction "2_7") (pintype "passive"))
      (node (ref "R34") (pin "8") (pinfunction "2_8") (pintype "passive"))
      (node (ref "R8") (pin "2") (pinfunction "2_2") (pintype "passive"))
      (node (ref "RST") (pin "1") (pinfunction "1_1") (pintype "passive"))
      (node (ref "STRIP") (pin "3") (pinfunction "3_3") (pintype "passive"))
      (node (ref "T1") (pin "E") (pinfunction "E_E") (pintype "passive"))
      (node (ref "T2") (pin "E") (pinfunction "E_E") (pintype "passive"))
      (node (ref "U1") (pin "15") (pinfunction "GND_15") (pintype "bidirectional"))
      (node (ref "U1") (pin "23") (pinfunction "GND_23") (pintype "bidirectional"))
      (node (ref "U1") (pin "35") (pinfunction "GND_35") (pintype "bidirectional"))
      (node (ref "U1") (pin "43") (pinfunction "GND_43") (pintype "bidirectional"))
      (node (ref "U1") (pin "5") (pinfunction "UGND_5") (pintype "bidirectional"))
      (node (ref "U10") (pin "10") (pinfunction "GND_10") (pintype "power_in"))
      (node (ref "U10") (pin "11") (pinfunction "GND_11") (pintype "power_in"))
      (node (ref "U10") (pin "7") (pinfunction "GND_7") (pintype "power_in"))
      (node (ref "U11") (pin "P$7") (pinfunction "GND_P$7") (pintype "power_in"))
      (node (ref "U6") (pin "16") (pinfunction "DGND_16") (pintype "power_in"))
      (node (ref "U6") (pin "20") (pinfunction "DGND_20") (pintype "power_in"))
      (node (ref "U6") (pin "21") (pinfunction "DGND_21") (pintype "power_in"))
      (node (ref "U6") (pin "22") (pinfunction "DGND_22") (pintype "power_in"))
      (node (ref "U6") (pin "35") (pinfunction "GND_35") (pintype "power_in"))
      (node (ref "U6") (pin "4") (pinfunction "DGND_4") (pintype "power_in"))
      (node (ref "U7") (pin "2") (pinfunction "GND_2") (pintype "bidirectional"))
      (node (ref "U9") (pin "P$10") (pinfunction "RSVRD3(GND)_P$10") (pintype "bidirectional"))
      (node (ref "U9") (pin "P$11") (pinfunction "RSVRD4(GND)_P$11") (pintype "bidirectional"))
      (node (ref "U9") (pin "P$12") (pinfunction "RSVRD5(GND)_P$12") (pintype "bidirectional"))
      (node (ref "U9") (pin "P$13") (pinfunction "GND_P$13") (pintype "bidirectional"))
      (node (ref "U9") (pin "P$15") (pinfunction "RSVRD6(VDD)_P$15") (pintype "bidirectional"))
      (node (ref "U9") (pin "P$8") (pinfunction "RSVRD1(GND)_P$8") (pintype "bidirectional"))
      (node (ref "U9") (pin "P$9") (pinfunction "RSVRD2(GND)_P$9") (pintype "bidirectional"))
      (node (ref "USB") (pin "BODY@1") (pinfunction "BODY_BODY@1") (pintype "tri_state"))
      (node (ref "USB") (pin "BODY@2") (pinfunction "BODY_BODY@2") (pintype "tri_state"))
      (node (ref "USB") (pin "BODY@3") (pinfunction "BODY_BODY@3") (pintype "tri_state"))
      (node (ref "USB") (pin "BODY@4") (pinfunction "BODY_BODY@4") (pintype "tri_state"))
      (node (ref "USB") (pin "P5") (pinfunction "GND_P5") (pintype "bidirectional"))
    )
    (net (code "17") (name "GPIO0") (class "Default")
      (node (ref "R34") (pin "3") (pinfunction "1_3") (pintype "passive"))
      (node (ref "U6") (pin "33") (pinfunction "GPIO0_33") (pintype "bidirectional"))
    )
    (net (code "18") (name "GPIO1") (class "Default")
      (node (ref "R34") (pin "2") (pinfunction "1_2") (pintype "passive"))
      (node (ref "U6") (pin "34") (pinfunction "GPIO1_34") (pintype "bidirectional"))
    )
    (net (code "19") (name "GPIO2") (class "Default")
      (node (ref "R21") (pin "4") (pinfunction "1_4") (pintype "passive"))
      (node (ref "U6") (pin "9") (pinfunction "GPIO2/DCLK_9") (pintype "bidirectional"))
    )
    (net (code "20") (name "GPIO3") (class "Default")
      (node (ref "R21") (pin "3") (pinfunction "1_3") (pintype "passive"))
      (node (ref "U6") (pin "10") (pinfunction "GPIO3/SDATA_10") (pintype "bidirectional"))
    )
    (net (code "21") (name "GPIO4") (class "Default")
      (node (ref "R34") (pin "1") (pinfunction "1_1") (pintype "passive"))
      (node (ref "U6") (pin "36") (pinfunction "GPIO4/I2S_LROUT_36") (pintype "bidirectional"))
    )
    (net (code "22") (name "GPIO5") (class "Default")
      (node (ref "R34") (pin "4") (pinfunction "1_4") (pintype "passive"))
      (node (ref "U6") (pin "25") (pinfunction "GPIO5/I2S_MCLK_25") (pintype "bidirectional"))
    )
    (net (code "23") (name "GPIO6") (class "Default")
      (node (ref "R21") (pin "2") (pinfunction "1_2") (pintype "passive"))
      (node (ref "U6") (pin "11") (pinfunction "GPIO6/I2S_SCLK_11") (pintype "bidirectional"))
    )
    (net (code "24") (name "GPIO7") (class "Default")
      (node (ref "R21") (pin "1") (pinfunction "1_1") (pintype "passive"))
      (node (ref "U6") (pin "12") (pinfunction "GPIO7/I2S_SDATA_12") (pintype "bidirectional"))
    )
    (net (code "25") (name "GYR") (class "Default")
      (node (ref "J_GYR") (pin "2") (pinfunction "2_2") (pintype "passive"))
      (node (ref "U1") (pin "29") (pinfunction "PB5(ADC12)_29") (pintype "bidirectional"))
    )
    (net (code "26") (name "GYR_INT") (class "Default")
      (node (ref "J_GYR") (pin "1") (pinfunction "1_1") (pintype "passive"))
      (node (ref "U9") (pin "P$7") (pinfunction "INT1_P$7") (pintype "bidirectional"))
    )
    (net (code "27") (name "GYR_RDY") (class "Default")
      (node (ref "J_GYR") (pin "3") (pinfunction "3_3") (pintype "passive"))
      (node (ref "U9") (pin "P$6") (pinfunction "DRDY/INT2_P$6") (pintype "bidirectional"))
    )
    (net (code "28") (name "LED") (class "Default")
      (node (ref "R5") (pin "1") (pinfunction "1_1") (pintype "passive"))
      (node (ref "U1") (pin "31") (pinfunction "PC6_31") (pintype "bidirectional"))
    )
    (net (code "29") (name "LED_STRIP") (class "Default")
      (node (ref "STRIP") (pin "2") (pinfunction "2_2") (pintype "passive"))
      (node (ref "U1") (pin "27") (pinfunction "PD7(ADC10)_27") (pintype "bidirectional"))
    )
    (net (code "30") (name "LEFT") (class "Default")
      (node (ref "R17") (pin "2") (pinfunction "2_2") (pintype "passive"))
      (node (ref "R19") (pin "2") (pinfunction "2_2") (pintype "passive"))
      (node (ref "U6") (pin "46") (pinfunction "LEFT_46") (pintype "bidirectional"))
    )
    (net (code "31") (name "LINE+") (class "Default")
      (node (ref "J_AIN") (pin "3") (pinfunction "3_3") (pintype "passive"))
      (node (ref "LINE+") (pin "1") (pinfunction "P_1") (pintype "passive"))
    )
    (net (code "32") (name "LINE-") (class "Default")
      (node (ref "LINE-") (pin "1") (pinfunction "P_1") (pintype "passive"))
      (node (ref "U6") (pin "48") (pinfunction "LINE2_48") (pintype "bidirectional"))
    )
    (net (code "33") (name "LSM") (class "Default")
      (node (ref "J_LSM") (pin "2") (pinfunction "2_2") (pintype "passive"))
      (node (ref "U1") (pin "28") (pinfunction "PB4(ADC11)_28") (pintype "bidirectional"))
    )
    (net (code "34") (name "LSM_DRDY") (class "Default")
      (node (ref "J_LSM") (pin "3") (pinfunction "3_3") (pintype "passive"))
      (node (ref "U10") (pin "9") (pinfunction "DRDY_9") (pintype "output"))
    )
    (net (code "35") (name "LSM_INT1") (class "Default")
      (node (ref "U1") (pin "1") (pinfunction "PE6_1") (pintype "bidirectional"))
      (node (ref "U10") (pin "5") (pinfunction "INT1_5") (pintype "output"))
    )
    (net (code "36") (name "LSM_INT2") (class "Default")
      (node (ref "J_LSM") (pin "1") (pinfunction "1_1") (pintype "passive"))
      (node (ref "U10") (pin "4") (pinfunction "INT2_4") (pintype "output"))
    )
    (net (code "37") (name "L_OUT") (class "Default")
      (node (ref "C12") (pin "2") (pinfunction "2_2") (pintype "passive"))
      (node (ref "C28") (pin "-") (pinfunction "-_-") (pintype "passive"))
    )
    (net (code "38") (name "M+") (class "Default")
      (node (ref "C24") (pin "1") (pinfunction "1_1") (pintype "passive"))
      (node (ref "C38") (pin "2") (pinfunction "2_2") (pintype "passive"))
      (node (ref "MIC") (pin "+") (pinfunction "1_+") (pintype "passive"))
      (node (ref "R30") (pin "2") (pinfunction "2_2") (pintype "passive"))
    )
    (net (code "39") (name "M-") (class "Default")
      (node (ref "C25") (pin "1") (pinfunction "1_1") (pintype "passive"))
      (node (ref "C38") (pin "1") (pinfunction "1_1") (pintype "passive"))
      (node (ref "MIC") (pin "-") (pinfunction "2_-") (pintype "passive"))
      (node (ref "R31") (pin "1") (pinfunction "1_1") (pintype "passive"))
    )
    (net (code "40") (name "MIC+") (class "Default")
      (node (ref "C24") (pin "2") (pinfunction "2_2") (pintype "passive"))
      (node (ref "J_AIN") (pin "1") (pinfunction "1_1") (pintype "passive"))
    )
    (net (code "41") (name "MIC-") (class "Default")
      (node (ref "C25") (pin "2") (pinfunction "2_2") (pintype "passive"))
      (node (ref "U6") (pin "2") (pinfunction "MIC_N_2") (pintype "bidirectional"))
    )
    (net (code "42") (name "MISO") (class "Default")
      (node (ref "ISP6") (pin "1") (pinfunction "1_1") (pintype "passive"))
      (node (ref "MICROSD") (pin "7") (pinfunction "DATA_OUT_7") (pintype "output"))
      (node (ref "U1") (pin "11") (pinfunction "PB3(MISO)_11") (pintype "bidirectional"))
      (node (ref "U6") (pin "30") (pinfunction "SO_30") (pintype "bidirectional"))
    )
    (net (code "43") (name "MOSI") (class "Default")
      (node (ref "ISP6") (pin "4") (pinfunction "4_4") (pintype "passive"))
      (node (ref "MICROSD") (pin "3") (pinfunction "DATA_IN_3") (pintype "input"))
      (node (ref "U1") (pin "10") (pinfunction "PB2(MOSI)_10") (pintype "bidirectional"))
      (node (ref "U6") (pin "29") (pinfunction "SI_29") (pintype "bidirectional"))
    )
    (net (code "44") (name "Net-(AMPLIFIER-OUTL+)") (class "Default")
      (node (ref "AMPLIFIER") (pin "13") (pinfunction "OUTL+_13") (pintype "bidirectional"))
      (node (ref "OUTL+") (pin "1") (pinfunction "P_1") (pintype "passive"))
    )
    (net (code "45") (name "Net-(AMPLIFIER-OUTL-)") (class "Default")
      (node (ref "AMPLIFIER") (pin "14") (pinfunction "OUTL-_14") (pintype "bidirectional"))
      (node (ref "OUTL-") (pin "1") (pinfunction "P_1") (pintype "passive"))
    )
    (net (code "46") (name "Net-(AMPLIFIER-OUTR+)") (class "Default")
      (node (ref "AMPLIFIER") (pin "10") (pinfunction "OUTR+_10") (pintype "bidirectional"))
      (node (ref "OUTR+") (pin "1") (pinfunction "P_1") (pintype "passive"))
    )
    (net (code "47") (name "Net-(AMPLIFIER-OUTR-)") (class "Default")
      (node (ref "AMPLIFIER") (pin "9") (pinfunction "OUTR-_9") (pintype "bidirectional"))
      (node (ref "OUTR-") (pin "1") (pinfunction "P_1") (pintype "passive"))
    )
    (net (code "48") (name "Net-(BAT+-P)") (class "Default")
      (node (ref "BAT+") (pin "1") (pinfunction "P_1") (pintype "passive"))
      (node (ref "IO1") (pin "3") (pinfunction "VBAT_3") (pintype "bidirectional"))
    )
    (net (code "49") (name "Net-(C20-Pad2)") (class "Default")
      (node (ref "C20") (pin "2") (pinfunction "2_2") (pintype "passive"))
      (node (ref "R17") (pin "1") (pinfunction "1_1") (pintype "passive"))
    )
    (net (code "50") (name "Net-(C21-Pad2)") (class "Default")
      (node (ref "C21") (pin "2") (pinfunction "2_2") (pintype "passive"))
      (node (ref "R18") (pin "1") (pinfunction "1_1") (pintype "passive"))
    )
    (net (code "51") (name "Net-(C26-Pad+)") (class "Default")
      (node (ref "C26") (pin "+") (pinfunction "+_+") (pintype "passive"))
      (node (ref "C37") (pin "+") (pinfunction "+_+") (pintype "passive"))
      (node (ref "R29") (pin "1") (pinfunction "1_1") (pintype "passive"))
      (node (ref "R30") (pin "1") (pinfunction "1_1") (pintype "passive"))
    )
    (net (code "52") (name "Net-(C28-Pad+)") (class "Default")
      (node (ref "C28") (pin "+") (pinfunction "+_+") (pintype "passive"))
      (node (ref "R19") (pin "1") (pinfunction "1_1") (pintype "passive"))
    )
    (net (code "53") (name "Net-(C29-Pad+)") (class "Default")
      (node (ref "C29") (pin "+") (pinfunction "+_+") (pintype "passive"))
      (node (ref "R20") (pin "1") (pinfunction "1_1") (pintype "passive"))
    )
    (net (code "54") (name "Net-(C31-Pad1)") (class "Default")
      (node (ref "C31") (pin "1") (pinfunction "1_1") (pintype "passive"))
      (node (ref "R27") (pin "2") (pinfunction "2_2") (pintype "passive"))
    )
    (net (code "55") (name "Net-(C37-Pad-)") (class "Default")
      (node (ref "C37") (pin "-") (pinfunction "-_-") (pintype "passive"))
      (node (ref "R31") (pin "2") (pinfunction "2_2") (pintype "passive"))
      (node (ref "R32") (pin "2") (pinfunction "2_2") (pintype "passive"))
    )
    (net (code "56") (name "Net-(CHG+-P)") (class "Default")
      (node (ref "C16") (pin "2") (pinfunction "2_2") (pintype "passive"))
      (node (ref "CHG+") (pin "1") (pinfunction "P_1") (pintype "passive"))
      (node (ref "IC2") (pin "4") (pinfunction "DC_4") (pintype "input"))
      (node (ref "R13") (pin "2") (pinfunction "2_2") (pintype "passive"))
    )
    (net (code "57") (name "Net-(D1-A2)") (class "Default")
      (node (ref "D1") (pin "2") (pinfunction "A2_2") (pintype "passive"))
      (node (ref "WUP") (pin "1") (pinfunction "P_1") (pintype "passive"))
    )
    (net (code "58") (name "Net-(D1-CC)") (class "Default")
      (node (ref "D1") (pin "3") (pinfunction "CC_3") (pintype "passive"))
      (node (ref "R28") (pin "1") (pinfunction "1_1") (pintype "passive"))
      (node (ref "R4") (pin "2") (pinfunction "2_2") (pintype "passive"))
    )
    (net (code "59") (name "Net-(D2-AA)") (class "Default")
      (node (ref "D2") (pin "3") (pinfunction "AA_3") (pintype "passive"))
      (node (ref "Q2") (pin "1") (pinfunction "G_1") (pintype "passive"))
      (node (ref "R10") (pin "1") (pinfunction "1_1") (pintype "passive"))
      (node (ref "T1") (pin "C") (pinfunction "C_C") (pintype "passive"))
    )
    (net (code "60") (name "Net-(D3-PadA)") (class "Default")
      (node (ref "D3") (pin "A") (pinfunction "A_A") (pintype "passive"))
      (node (ref "R5") (pin "2") (pinfunction "2_2") (pintype "passive"))
    )
    (net (code "61") (name "Net-(FB3-P$1)") (class "Default")
      (node (ref "C39") (pin "2") (pinfunction "2_2") (pintype "passive"))
      (node (ref "C40") (pin "2") (pinfunction "2_2") (pintype "passive"))
      (node (ref "FB3") (pin "1") (pinfunction "P$1_1") (pintype "passive"))
      (node (ref "STRIP") (pin "1") (pinfunction "1_1") (pintype "passive"))
    )
    (net (code "62") (name "Net-(IO1-X1)") (class "Default")
      (node (ref "C43") (pin "1") (pinfunction "1_1") (pintype "passive"))
      (node (ref "IO1") (pin "1") (pinfunction "X1_1") (pintype "bidirectional"))
      (node (ref "Q6") (pin "2") (pinfunction "2_2") (pintype "passive"))
    )
    (net (code "63") (name "Net-(IO1-X2)") (class "Default")
      (node (ref "C44") (pin "1") (pinfunction "1_1") (pintype "passive"))
      (node (ref "IO1") (pin "2") (pinfunction "X2_2") (pintype "bidirectional"))
      (node (ref "Q6") (pin "1") (pinfunction "1_1") (pintype "passive"))
    )
    (net (code "64") (name "Net-(J_GAIN-Pad1)") (class "Default")
      (node (ref "J_GAIN") (pin "1") (pinfunction "1_1") (pintype "passive"))
      (node (ref "R22") (pin "1") (pinfunction "1_1") (pintype "passive"))
    )
    (net (code "65") (name "Net-(J_GAIN-Pad3)") (class "Default")
      (node (ref "J_GAIN") (pin "3") (pinfunction "3_3") (pintype "passive"))
      (node (ref "R23") (pin "2") (pinfunction "2_2") (pintype "passive"))
    )
    (net (code "66") (name "Net-(R4-Pad1)") (class "Default")
      (node (ref "R4") (pin "1") (pinfunction "1_1") (pintype "passive"))
      (node (ref "T1") (pin "B") (pinfunction "B_B") (pintype "passive"))
    )
    (net (code "67") (name "Net-(R24-Pad2)") (class "Default")
      (node (ref "R24") (pin "2") (pinfunction "2_2") (pintype "passive"))
      (node (ref "T2") (pin "B") (pinfunction "B_B") (pintype "passive"))
    )
    (net (code "68") (name "Net-(U1-AREF)") (class "Default")
      (node (ref "C4") (pin "1") (pinfunction "1_1") (pintype "passive"))
      (node (ref "U1") (pin "42") (pinfunction "AREF_42") (pintype "bidirectional"))
    )
    (net (code "69") (name "Net-(U1-D+)") (class "Default")
      (node (ref "R1") (pin "1") (pinfunction "1_1") (pintype "passive"))
      (node (ref "U1") (pin "4") (pinfunction "D+_4") (pintype "bidirectional"))
    )
    (net (code "70") (name "Net-(U1-D-)") (class "Default")
      (node (ref "R2") (pin "1") (pinfunction "1_1") (pintype "passive"))
      (node (ref "U1") (pin "3") (pinfunction "D-_3") (pintype "bidirectional"))
    )
    (net (code "71") (name "Net-(U1-PF0(ADC0))") (class "Default")
      (node (ref "ADC0") (pin "TP") (pinfunction "TP_TP") (pintype "input"))
      (node (ref "U1") (pin "41") (pinfunction "PF0(ADC0)_41") (pintype "bidirectional"))
    )
    (net (code "72") (name "Net-(U1-PF1(ADC1))") (class "Default")
      (node (ref "ADC1") (pin "TP") (pinfunction "TP_TP") (pintype "input"))
      (node (ref "U1") (pin "40") (pinfunction "PF1(ADC1)_40") (pintype "bidirectional"))
    )
    (net (code "73") (name "Net-(U1-UCAP)") (class "Default")
      (node (ref "C1") (pin "1") (pinfunction "1_1") (pintype "passive"))
      (node (ref "U1") (pin "6") (pinfunction "UCAP_6") (pintype "bidirectional"))
    )
    (net (code "74") (name "Net-(U1-XTAL1)") (class "Default")
      (node (ref "C8") (pin "1") (pinfunction "1_1") (pintype "passive"))
      (node (ref "U1") (pin "17") (pinfunction "XTAL1_17") (pintype "bidirectional"))
      (node (ref "Y1") (pin "3") (pinfunction "2_3") (pintype "passive"))
    )
    (net (code "75") (name "Net-(U1-XTAL2)") (class "Default")
      (node (ref "C9") (pin "1") (pinfunction "1_1") (pintype "passive"))
      (node (ref "U1") (pin "16") (pinfunction "XTAL2_16") (pintype "bidirectional"))
      (node (ref "Y1") (pin "1") (pinfunction "1_1") (pintype "passive"))
    )
    (net (code "76") (name "Net-(U6-MIC_P{slash}LINEIN)") (class "Default")
      (node (ref "J_AIN") (pin "2") (pinfunction "2_2") (pintype "passive"))
      (node (ref "U6") (pin "1") (pinfunction "MIC_P/LINEIN_1") (pintype "bidirectional"))
    )
    (net (code "77") (name "Net-(U6-XTALIN)") (class "Default")
      (node (ref "C18") (pin "1") (pinfunction "1_1") (pintype "passive"))
      (node (ref "R15") (pin "1") (pinfunction "1_1") (pintype "passive"))
      (node (ref "U6") (pin "18") (pinfunction "XTALIN_18") (pintype "input"))
      (node (ref "Y2") (pin "2") (pinfunction "2_2") (pintype "passive"))
    )
    (net (code "78") (name "Net-(U6-XTALOUT)") (class "Default")
      (node (ref "C19") (pin "1") (pinfunction "1_1") (pintype "passive"))
      (node (ref "R15") (pin "2") (pinfunction "2_2") (pintype "passive"))
      (node (ref "U6") (pin "17") (pinfunction "XTALOUT_17") (pintype "output"))
      (node (ref "Y2") (pin "1") (pinfunction "1_1") (pintype "passive"))
    )
    (net (code "79") (name "Net-(U9-CS)") (class "Default")
      (node (ref "R25") (pin "1") (pinfunction "1_1") (pintype "passive"))
      (node (ref "U9") (pin "P$5") (pinfunction "CS_P$5") (pintype "bidirectional"))
    )
    (net (code "80") (name "Net-(U9-PLLFILT)") (class "Default")
      (node (ref "C30") (pin "2") (pinfunction "2_2") (pintype "passive"))
      (node (ref "C31") (pin "2") (pinfunction "2_2") (pintype "passive"))
      (node (ref "U9") (pin "P$14") (pinfunction "PLLFILT_P$14") (pintype "bidirectional"))
    )
    (net (code "81") (name "Net-(U9-SDO{slash}SAO)") (class "Default")
      (node (ref "R26") (pin "1") (pinfunction "1_1") (pintype "passive"))
      (node (ref "U9") (pin "P$4") (pinfunction "SDO/SAO_P$4") (pintype "bidirectional"))
    )
    (net (code "82") (name "Net-(U10-C1)") (class "Default")
      (node (ref "C35") (pin "1") (pinfunction "1_1") (pintype "passive"))
      (node (ref "U10") (pin "6") (pinfunction "C1_6") (pintype "bidirectional"))
    )
    (net (code "83") (name "Net-(U10-SETC)") (class "Default")
      (node (ref "C36") (pin "2") (pinfunction "2_2") (pintype "passive"))
      (node (ref "U10") (pin "13") (pinfunction "SETC_13") (pintype "bidirectional"))
    )
    (net (code "84") (name "Net-(U10-SETP)") (class "Default")
      (node (ref "C36") (pin "1") (pinfunction "1_1") (pintype "passive"))
      (node (ref "U10") (pin "12") (pinfunction "SETP_12") (pintype "bidirectional"))
    )
    (net (code "85") (name "Net-(VIB--P)") (class "Default")
      (node (ref "T2") (pin "C") (pinfunction "C_C") (pintype "passive"))
      (node (ref "VIB-") (pin "1") (pinfunction "P_1") (pintype "passive"))
    )
    (net (code "86") (name "PWR_CMD") (class "Default")
      (node (ref "D1") (pin "1") (pinfunction "A1_1") (pintype "passive"))
      (node (ref "U1") (pin "25") (pinfunction "PD4(ADC8)_25") (pintype "bidirectional"))
    )
    (net (code "87") (name "RESET") (class "Default")
      (node (ref "ISP6") (pin "5") (pinfunction "5_5") (pintype "passive"))
      (node (ref "R3") (pin "2") (pinfunction "2_2") (pintype "passive"))
      (node (ref "RST") (pin "3") (pinfunction "2_3") (pintype "passive"))
      (node (ref "U1") (pin "13") (pinfunction "~{RESET}_13") (pintype "bidirectional"))
    )
    (net (code "88") (name "RIGHT") (class "Default")
      (node (ref "R18") (pin "2") (pinfunction "2_2") (pintype "passive"))
      (node (ref "R20") (pin "2") (pinfunction "2_2") (pintype "passive"))
      (node (ref "U6") (pin "39") (pinfunction "RIGHT_39") (pintype "bidirectional"))
    )
    (net (code "89") (name "RST") (class "Default")
      (node (ref "C27") (pin "2") (pinfunction "2_2") (pintype "passive"))
      (node (ref "R16") (pin "1") (pinfunction "1_1") (pintype "passive"))
      (node (ref "U1") (pin "32") (pinfunction "PC7_32") (pintype "bidirectional"))
      (node (ref "U6") (pin "3") (pinfunction "XRESET_3") (pintype "bidirectional"))
    )
    (net (code "90") (name "R_OUT") (class "Default")
      (node (ref "C14") (pin "2") (pinfunction "2_2") (pintype "passive"))
      (node (ref "C29") (pin "-") (pinfunction "-_-") (pintype "passive"))
    )
    (net (code "91") (name "SCL") (class "Default")
      (node (ref "EXT") (pin "5") (pinfunction "5_5") (pintype "passive"))
      (node (ref "IO1") (pin "6") (pinfunction "SCL_6") (pintype "bidirectional"))
      (node (ref "U1") (pin "18") (pinfunction "PD0(SCL)_18") (pintype "bidirectional"))
      (node (ref "U10") (pin "2") (pinfunction "SCL_2") (pintype "bidirectional"))
      (node (ref "U11") (pin "P$5") (pinfunction "SCL_P$5") (pintype "bidirectional"))
      (node (ref "U9") (pin "P$2") (pinfunction "SCL/SPC_P$2") (pintype "bidirectional"))
    )
    (net (code "92") (name "SCLK") (class "Default")
      (node (ref "ISP6") (pin "3") (pinfunction "3_3") (pintype "passive"))
      (node (ref "MICROSD") (pin "5") (pinfunction "SCLK_5") (pintype "input"))
      (node (ref "U1") (pin "9") (pinfunction "PB1(SCK)_9") (pintype "bidirectional"))
      (node (ref "U6") (pin "28") (pinfunction "SCLK_28") (pintype "bidirectional"))
    )
    (net (code "93") (name "SDA") (class "Default")
      (node (ref "EXT") (pin "4") (pinfunction "4_4") (pintype "passive"))
      (node (ref "IO1") (pin "5") (pinfunction "SDA_5") (pintype "bidirectional"))
      (node (ref "U1") (pin "19") (pinfunction "PD1(SDA)_19") (pintype "bidirectional"))
      (node (ref "U10") (pin "3") (pinfunction "SDA_3") (pintype "bidirectional"))
      (node (ref "U11") (pin "P$6") (pinfunction "SDA_P$6") (pintype "bidirectional"))
      (node (ref "U9") (pin "P$3") (pinfunction "SDA/SDI/SDO_P$3") (pintype "bidirectional"))
    )
    (net (code "94") (name "SDCS") (class "Default")
      (node (ref "MICROSD") (pin "2") (pinfunction "CS_2") (pintype "input"))
      (node (ref "U1") (pin "22") (pinfunction "PD5_22") (pintype "bidirectional"))
    )
    (net (code "95") (name "SD_DETECT") (class "Default")
      (node (ref "MICROSD") (pin "CD1") (pinfunction "CARD_DETECT_CD1") (pintype "passive"))
      (node (ref "R6") (pin "2") (pinfunction "2_2") (pintype "passive"))
      (node (ref "U1") (pin "39") (pinfunction "PF4(ADC4)_39") (pintype "bidirectional"))
    )
    (net (code "96") (name "SHUTDOWN") (class "Default")
      (node (ref "AMPLIFIER") (pin "2") (pinfunction "SHDN_2") (pintype "input"))
      (node (ref "R33") (pin "2") (pinfunction "2_2") (pintype "passive"))
      (node (ref "U1") (pin "33") (pinfunction "PE2/~{HWB}_33") (pintype "bidirectional"))
    )
    (net (code "97") (name "TIMER") (class "Default")
      (node (ref "D2") (pin "1") (pinfunction "K1_1") (pintype "passive"))
      (node (ref "IO1") (pin "7") (pinfunction "MFP_7") (pintype "bidirectional"))
    )
    (net (code "98") (name "VBUS") (class "Default")
      (node (ref "C17") (pin "2") (pinfunction "2_2") (pintype "passive"))
      (node (ref "IC2") (pin "1") (pinfunction "USB_1") (pintype "input"))
      (node (ref "R7") (pin "1") (pinfunction "1_1") (pintype "passive"))
      (node (ref "U1") (pin "2") (pinfunction "UVCC_2") (pintype "bidirectional"))
      (node (ref "U1") (pin "7") (pinfunction "VBUS_7") (pintype "bidirectional"))
      (node (ref "USB") (pin "P1") (pinfunction "VUSB_P1") (pintype "bidirectional"))
    )
    (net (code "99") (name "VCC") (class "Default")
      (node (ref "C3") (pin "2") (pinfunction "2_2") (pintype "passive"))
      (node (ref "C41") (pin "2") (pinfunction "2_2") (pintype "passive"))
      (node (ref "C5") (pin "2") (pinfunction "2_2") (pintype "passive"))
      (node (ref "EXT") (pin "3") (pinfunction "3_3") (pintype "passive"))
      (node (ref "FB3") (pin "2") (pinfunction "P$2_2") (pintype "passive"))
      (node (ref "IC2") (pin "5") (pinfunction "BAT_5") (pintype "passive"))
      (node (ref "ISP6") (pin "2") (pinfunction "2_2") (pintype "passive"))
      (node (ref "J_PRG") (pin "1") (pinfunction "1_1") (pintype "passive"))
      (node (ref "Q2") (pin "3") (pinfunction "D_3") (pintype "passive"))
      (node (ref "R10") (pin "2") (pinfunction "2_2") (pintype "passive"))
      (node (ref "R11") (pin "2") (pinfunction "2_2") (pintype "passive"))
      (node (ref "R9") (pin "2") (pinfunction "2_2") (pintype "passive"))
      (node (ref "STEPUP+") (pin "1") (pinfunction "P_1") (pintype "passive"))
      (node (ref "STEPUP-") (pin "1") (pinfunction "P_1") (pintype "passive"))
      (node (ref "U7") (pin "3") (pinfunction "EN2_3") (pintype "bidirectional"))
      (node (ref "U7") (pin "4") (pinfunction "EN1_4") (pintype "bidirectional"))
      (node (ref "U7") (pin "5") (pinfunction "VIN_5") (pintype "bidirectional"))
      (node (ref "VIB+") (pin "1") (pinfunction "P_1") (pintype "passive"))
    )
    (net (code "100") (name "VIBRATOR") (class "Default")
      (node (ref "R24") (pin "1") (pinfunction "1_1") (pintype "passive"))
      (node (ref "U1") (pin "30") (pinfunction "PB6(ADC13)_30") (pintype "bidirectional"))
    )
    (net (code "101") (name "V_CHG") (class "Default")
      (node (ref "R13") (pin "1") (pinfunction "1_1") (pintype "passive"))
      (node (ref "R14") (pin "2") (pinfunction "2_2") (pintype "passive"))
      (node (ref "U1") (pin "37") (pinfunction "PF6(ADC6)_37") (pintype "bidirectional"))
    )
    (net (code "102") (name "V_PWR") (class "Default")
      (node (ref "R11") (pin "1") (pinfunction "1_1") (pintype "passive"))
      (node (ref "R12") (pin "2") (pinfunction "2_2") (pintype "passive"))
      (node (ref "U1") (pin "36") (pinfunction "PF7(ADC7)_36") (pintype "bidirectional"))
    )
    (net (code "103") (name "V_VBUS") (class "Default")
      (node (ref "R7") (pin "2") (pinfunction "2_2") (pintype "passive"))
      (node (ref "R8") (pin "1") (pinfunction "1_1") (pintype "passive"))
      (node (ref "U1") (pin "38") (pinfunction "PF5(ADC5)_38") (pintype "bidirectional"))
    )
    (net (code "104") (name "XDCS") (class "Default")
      (node (ref "U1") (pin "26") (pinfunction "PD6(ADC9)_26") (pintype "bidirectional"))
      (node (ref "U6") (pin "13") (pinfunction "XDCS/BSYNC_13") (pintype "bidirectional"))
    )
    (net (code "105") (name "unconnected-(H1-MOUNT-PadB3,0)") (class "Default")
      (node (ref "H1") (pin "B3,0") (pinfunction "MOUNT_B3,0") (pintype "passive"))
    )
    (net (code "106") (name "unconnected-(H2-MOUNT-PadB3,0)") (class "Default")
      (node (ref "H2") (pin "B3,0") (pinfunction "MOUNT_B3,0") (pintype "passive"))
    )
    (net (code "107") (name "unconnected-(H3-MOUNT-PadB3,0)") (class "Default")
      (node (ref "H3") (pin "B3,0") (pinfunction "MOUNT_B3,0") (pintype "passive"))
    )
    (net (code "108") (name "unconnected-(H4-MOUNT-PadB3,0)") (class "Default")
      (node (ref "H4") (pin "B3,0") (pinfunction "MOUNT_B3,0") (pintype "passive"))
    )
    (net (code "109") (name "unconnected-(MICROSD-CARD_DETECT1-PadCD2)") (class "Default")
      (node (ref "MICROSD") (pin "CD2") (pinfunction "CARD_DETECT1_CD2") (pintype "passive"))
    )
    (net (code "110") (name "unconnected-(MICROSD-DAT1-Pad8)") (class "Default")
      (node (ref "MICROSD") (pin "8") (pinfunction "DAT1_8") (pintype "bidirectional"))
    )
    (net (code "111") (name "unconnected-(MICROSD-DAT2-Pad1)") (class "Default")
      (node (ref "MICROSD") (pin "1") (pinfunction "DAT2_1") (pintype "bidirectional"))
    )
    (net (code "112") (name "unconnected-(U6-GBUF-Pad42)") (class "Default")
      (node (ref "U6") (pin "42") (pinfunction "GBUF_42") (pintype "bidirectional"))
    )
    (net (code "113") (name "unconnected-(U6-RCAP-Pad44)") (class "Default")
      (node (ref "U6") (pin "44") (pinfunction "RCAP_44") (pintype "bidirectional"))
    )
    (net (code "114") (name "unconnected-(U6-TX-Pad27)") (class "Default")
      (node (ref "U6") (pin "27") (pinfunction "TX_27") (pintype "bidirectional"))
    )
    (net (code "115") (name "unconnected-(U6-VCO-Pad15)") (class "Default")
      (node (ref "U6") (pin "15") (pinfunction "VCO_15") (pintype "bidirectional"))
    )
    (net (code "116") (name "unconnected-(U10-NC-Pad8)") (class "Default")
      (node (ref "U10") (pin "8") (pinfunction "NC_8") (pintype "bidirectional"))
    )
    (net (code "117") (name "unconnected-(U11-NC-PadP$1)") (class "Default")
      (node (ref "U11") (pin "P$1") (pinfunction "NC_P$1") (pintype "no_connect"))
    )
    (net (code "118") (name "unconnected-(U11-NC-PadP$4)") (class "Default")
      (node (ref "U11") (pin "P$4") (pinfunction "NC_P$4") (pintype "no_connect"))
    )
    (net (code "119") (name "unconnected-(USBB-USBID-PadP4)") (class "Default")
      (node (ref "USB") (pin "P4") (pinfunction "USBID_P4") (pintype "bidirectional"))
    )
  )
)
